# loki.net
KiCad netlist of a schematic drawn in EAGLE
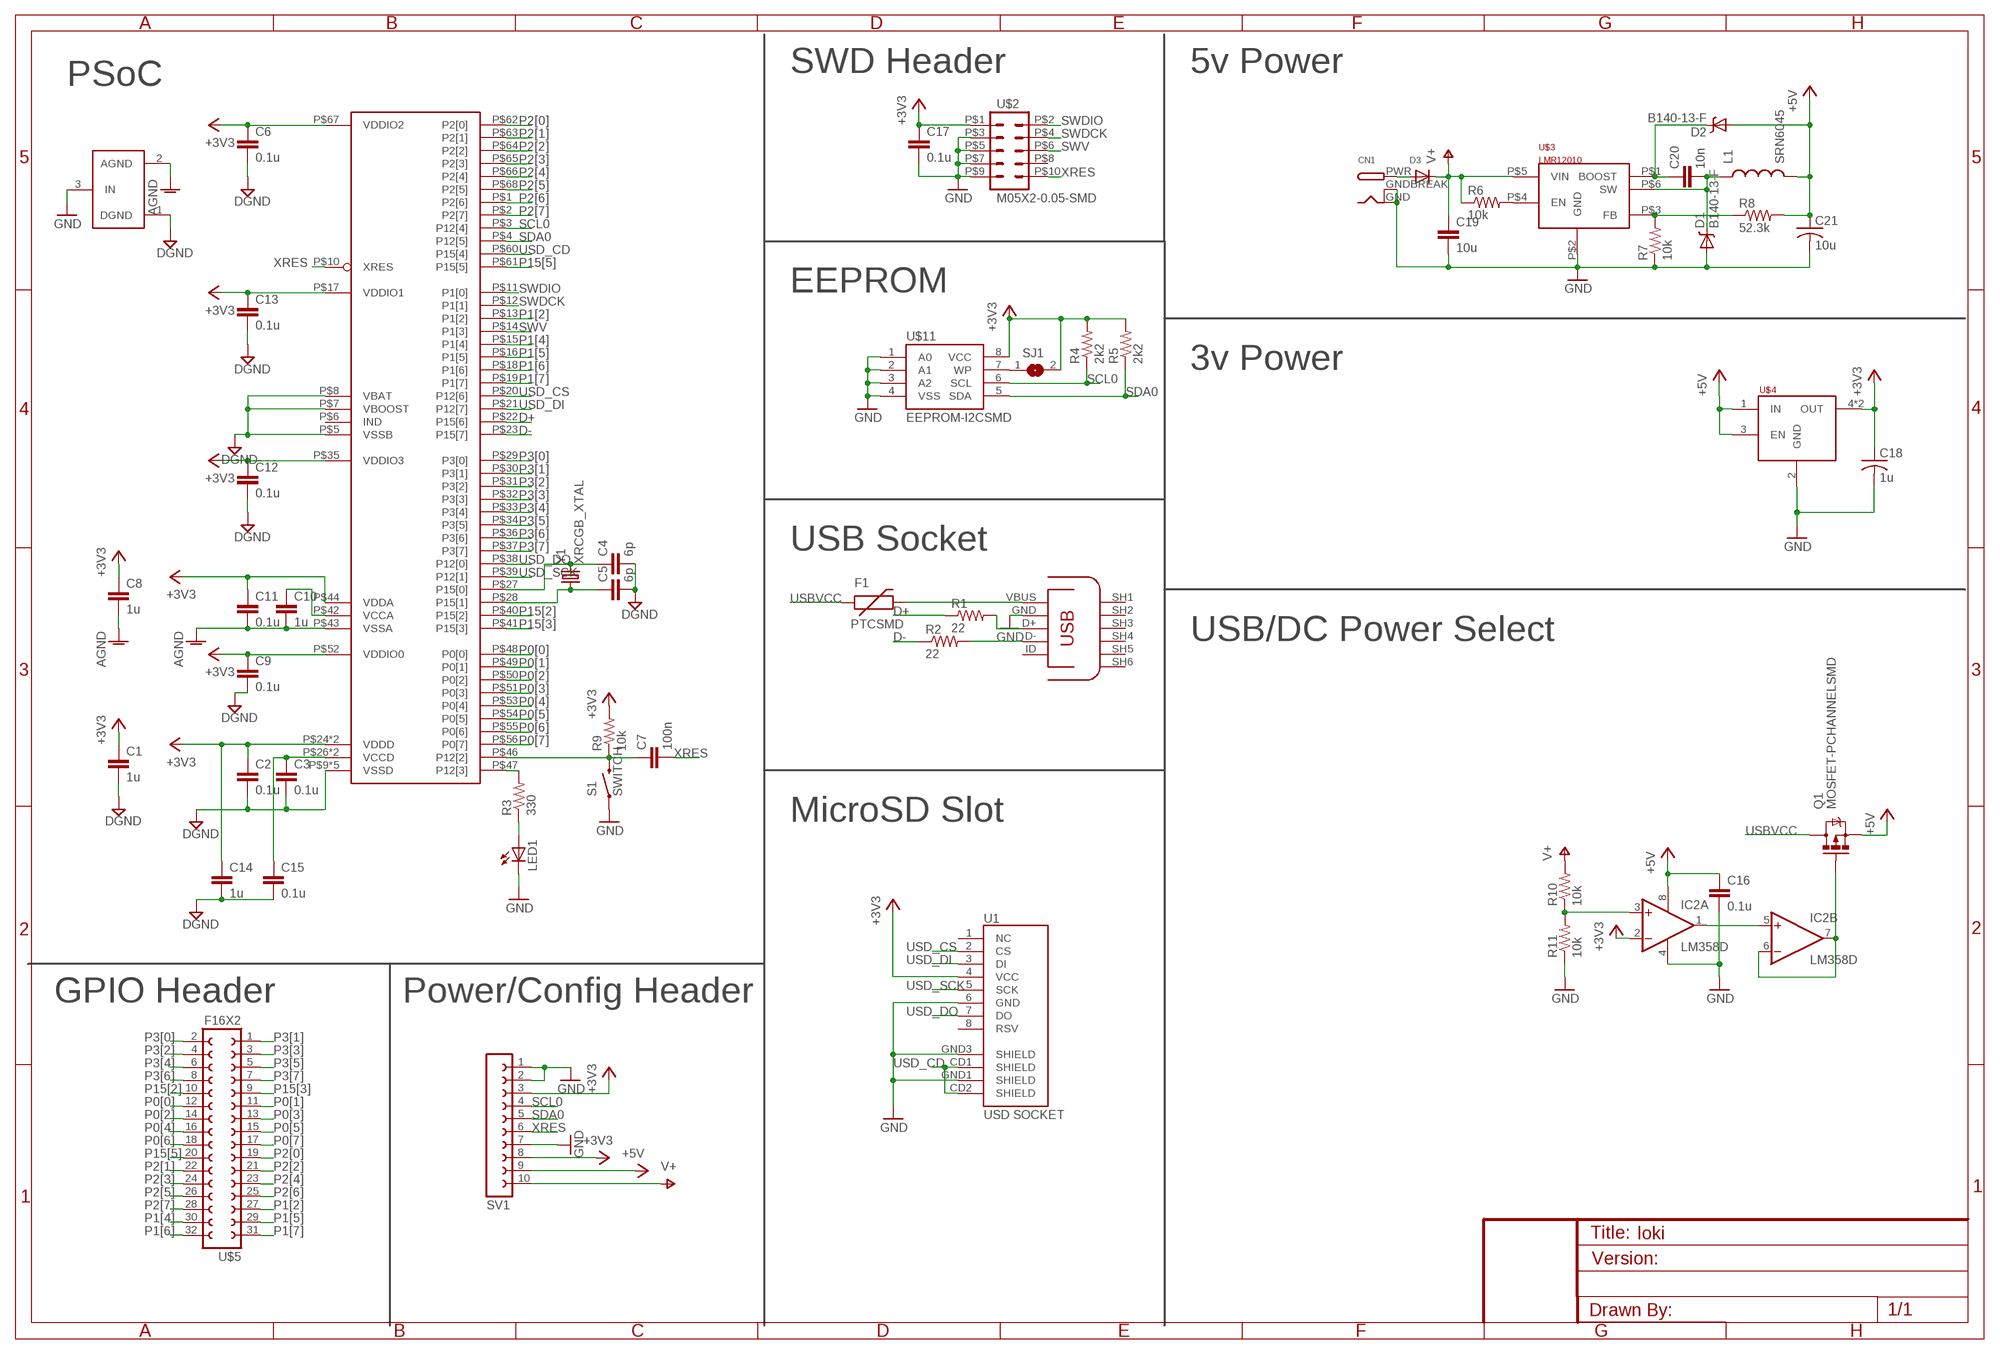
[diagram p0: schematic, sheet 1]

(export (version "E")
  (design (tool "Eeschema 10.0.6"))
  (components
    (comp (ref "C1")
      (value "1u")
      (footprint "eagle-import:C0603K")
      (libsource (lib "eagle-import") (part "C-EUC0603K"))
    )
    (comp (ref "C2")
      (value "0.1u")
      (footprint "eagle-import:C0603K")
      (libsource (lib "eagle-import") (part "C-EUC0603K"))
    )
    (comp (ref "C3")
      (value "0.1u")
      (footprint "eagle-import:C0603K")
      (libsource (lib "eagle-import") (part "C-EUC0603K"))
    )
    (comp (ref "C4")
      (value "6p")
      (footprint "eagle-import:C0603K")
      (libsource (lib "eagle-import") (part "C-EUC0603K"))
    )
    (comp (ref "C5")
      (value "6p")
      (footprint "eagle-import:C0603K")
      (libsource (lib "eagle-import") (part "C-EUC0603K"))
    )
    (comp (ref "C6")
      (value "0.1u")
      (footprint "eagle-import:C0603K")
      (libsource (lib "eagle-import") (part "C-EUC0603K"))
    )
    (comp (ref "C7")
      (value "100n")
      (footprint "eagle-import:C0603K")
      (libsource (lib "eagle-import") (part "C-EUC0603K"))
    )
    (comp (ref "C8")
      (value "1u")
      (footprint "eagle-import:C0603K")
      (libsource (lib "eagle-import") (part "C-EUC0603K"))
    )
    (comp (ref "C9")
      (value "0.1u")
      (footprint "eagle-import:C0603K")
      (libsource (lib "eagle-import") (part "C-EUC0603K"))
    )
    (comp (ref "C10")
      (value "1u")
      (footprint "eagle-import:C0603K")
      (libsource (lib "eagle-import") (part "C-EUC0603K"))
    )
    (comp (ref "C11")
      (value "0.1u")
      (footprint "eagle-import:C0603K")
      (libsource (lib "eagle-import") (part "C-EUC0603K"))
    )
    (comp (ref "C12")
      (value "0.1u")
      (footprint "eagle-import:C0603K")
      (libsource (lib "eagle-import") (part "C-EUC0603K"))
    )
    (comp (ref "C13")
      (value "0.1u")
      (footprint "eagle-import:C0603K")
      (libsource (lib "eagle-import") (part "C-EUC0603K"))
    )
    (comp (ref "C14")
      (value "1u")
      (footprint "eagle-import:C0603K")
      (libsource (lib "eagle-import") (part "C-EUC0603K"))
    )
    (comp (ref "C15")
      (value "0.1u")
      (footprint "eagle-import:C0603K")
      (libsource (lib "eagle-import") (part "C-EUC0603K"))
    )
    (comp (ref "C16")
      (value "0.1u")
      (footprint "eagle-import:0603-CAP")
      (libsource (lib "eagle-import") (part "CAP0603-CAP"))
    )
    (comp (ref "C17")
      (value "0.1u")
      (footprint "eagle-import:C0603K")
      (libsource (lib "eagle-import") (part "C-EUC0603K"))
    )
    (comp (ref "C18")
      (value "1u")
      (footprint "eagle-import:C0603")
      (libsource (lib "eagle-import") (part "C-USC0603"))
    )
    (comp (ref "C19")
      (value "10u")
      (footprint "eagle-import:C1210")
      (libsource (lib "eagle-import") (part "C-EUC1210"))
    )
    (comp (ref "C20")
      (value "10n")
      (footprint "eagle-import:C0805")
      (libsource (lib "eagle-import") (part "C-EUC0805"))
    )
    (comp (ref "C21")
      (value "10u")
      (footprint "eagle-import:C1206")
      (libsource (lib "eagle-import") (part "C-USC1206"))
    )
    (comp (ref "CN1")
      (value "DCBARRELPTH")
      (footprint "eagle-import:DCJACK_2MM_PTH")
      (libsource (lib "eagle-import") (part "DCBARRELPTH"))
    )
    (comp (ref "D1")
      (value "B140-13-F")
      (footprint "eagle-import:SMA-DIODE")
      (libsource (lib "eagle-import") (part "DIODE-SCHOTTKY_"))
    )
    (comp (ref "D2")
      (value "B140-13-F")
      (footprint "eagle-import:SMA-DIODE")
      (libsource (lib "eagle-import") (part "DIODE-SCHOTTKY_"))
    )
    (comp (ref "D3")
      (value "DIODESMA")
      (footprint "eagle-import:SMADIODE")
      (libsource (lib "eagle-import") (part "DIODESMA"))
    )
    (comp (ref "F1")
      (value "PTCSMD")
      (footprint "eagle-import:PTC-1206")
      (libsource (lib "eagle-import") (part "PTCSMD"))
    )
    (comp (ref "IC2")
      (value "LM358D")
      (footprint "eagle-import:SO08")
      (libsource (lib "eagle-import") (part "LM358D"))
    )
    (comp (ref "L1")
      (value "SRN6045")
      (footprint "eagle-import:SRN6045")
      (libsource (lib "eagle-import") (part "SRN6045"))
    )
    (comp (ref "LED1")
      (value "LEDCHIP-LED0805")
      (footprint "eagle-import:CHIP-LED0805")
      (libsource (lib "eagle-import") (part "LEDCHIP-LED0805"))
    )
    (comp (ref "Q1")
      (value "MOSFET-PCHANNELSMD")
      (footprint "eagle-import:SOT23-3")
      (libsource (lib "eagle-import") (part "MOSFET-PCHANNELSMD"))
    )
    (comp (ref "R1")
      (value "22")
      (footprint "eagle-import:0603-RES")
      (libsource (lib "eagle-import") (part "RESISTOR0603-RES"))
    )
    (comp (ref "R2")
      (value "22")
      (footprint "eagle-import:0603-RES")
      (libsource (lib "eagle-import") (part "RESISTOR0603-RES"))
    )
    (comp (ref "R3")
      (value "330")
      (footprint "eagle-import:R0603")
      (libsource (lib "eagle-import") (part "R-US_R0603"))
    )
    (comp (ref "R4")
      (value "2k2")
      (footprint "eagle-import:R0603")
      (libsource (lib "eagle-import") (part "R-US_R0603"))
    )
    (comp (ref "R5")
      (value "2k2")
      (footprint "eagle-import:R0603")
      (libsource (lib "eagle-import") (part "R-US_R0603"))
    )
    (comp (ref "R6")
      (value "10k")
      (footprint "eagle-import:R0603")
      (libsource (lib "eagle-import") (part "R-US_R0603"))
    )
    (comp (ref "R7")
      (value "10k")
      (footprint "eagle-import:R0603")
      (libsource (lib "eagle-import") (part "R-US_R0603"))
    )
    (comp (ref "R8")
      (value "52.3k")
      (footprint "eagle-import:R0603")
      (libsource (lib "eagle-import") (part "R-US_R0603"))
    )
    (comp (ref "R9")
      (value "10k")
      (footprint "eagle-import:R0603")
      (libsource (lib "eagle-import") (part "R-US_R0603"))
    )
    (comp (ref "R10")
      (value "10k")
      (footprint "eagle-import:R0603")
      (libsource (lib "eagle-import") (part "R-US_R0603"))
    )
    (comp (ref "R11")
      (value "10k")
      (footprint "eagle-import:R0603")
      (libsource (lib "eagle-import") (part "R-US_R0603"))
    )
    (comp (ref "S1")
      (value "SWITCH")
      (footprint "eagle-import:TACTILE_SWITCH_SMD")
      (libsource (lib "eagle-import") (part "SWITCH-MOMENTARY-2SMD"))
    )
    (comp (ref "SJ1") (value "SJ") (footprint "eagle-import:SJ") (libsource (lib "eagle-import") (part "SJ")))
    (comp (ref "SV1")
      (value "FE10-1")
      (footprint "eagle-import:FE10")
      (libsource (lib "eagle-import") (part "FE10-1"))
    )
    (comp (ref "U$1")
      (value "CY83XXX-68PIN")
      (footprint "eagle-import:QFN68")
      (libsource (lib "eagle-import") (part "CY83XXX-68PIN"))
    )
    (comp (ref "U$2")
      (value "M05X2-0.05-SMD")
      (footprint "eagle-import:PINHD-2X5-0.05-SMD")
      (libsource (lib "eagle-import") (part "M05X2-0.05-SMD"))
    )
    (comp (ref "U$3")
      (value "LMR12010")
      (footprint "eagle-import:TSOT-6")
      (libsource (lib "eagle-import") (part "LMR12010"))
    )
    (comp (ref "U$4")
      (value "TLV702XX")
      (footprint "eagle-import:SOT23-5")
      (libsource (lib "eagle-import") (part "TLV702XX"))
    )
    (comp (ref "U$5")
      (value "F16X2")
      (footprint "eagle-import:FE16-2")
      (libsource (lib "eagle-import") (part "F16X2"))
    )
    (comp (ref "U$7")
      (value "MICROUSB")
      (footprint "eagle-import:USB-MICROB")
      (libsource (lib "eagle-import") (part "MICROUSB"))
    )
    (comp (ref "U$9")
      (value "GND_CONNECT")
      (footprint "eagle-import:GND_CONNECT")
      (libsource (lib "eagle-import") (part "GND_CONNECT"))
    )
    (comp (ref "U$11")
      (value "EEPROM-I2CSMD")
      (footprint "eagle-import:SO08")
      (libsource (lib "eagle-import") (part "EEPROM-I2CSMD"))
    )
    (comp (ref "U1")
      (value "USD SOCKET")
      (footprint "eagle-import:MICRO-SD-SOCKET-PP")
      (libsource (lib "eagle-import") (part "USD-SOCKETNEW"))
    )
    (comp (ref "Y1")
      (value "XRCGB_XTAL")
      (footprint "eagle-import:XRCGB-XTAL")
      (libsource (lib "eagle-import") (part "XRCGB_XTAL"))
    )
  )
  (nets
    (net (code "1") (name "+3V3") (class "Default")
      (node (ref "C1") (pin "1") (pinfunction "1_1") (pintype "passive"))
      (node (ref "C11") (pin "1") (pinfunction "1_1") (pintype "passive"))
      (node (ref "C12") (pin "1") (pinfunction "1_1") (pintype "passive"))
      (node (ref "C13") (pin "1") (pinfunction "1_1") (pintype "passive"))
      (node (ref "C14") (pin "1") (pinfunction "1_1") (pintype "passive"))
      (node (ref "C17") (pin "1") (pinfunction "1_1") (pintype "passive"))
      (node (ref "C18") (pin "1") (pinfunction "1_1") (pintype "passive"))
      (node (ref "C2") (pin "1") (pinfunction "1_1") (pintype "passive"))
      (node (ref "C6") (pin "1") (pinfunction "1_1") (pintype "passive"))
      (node (ref "C8") (pin "1") (pinfunction "1_1") (pintype "passive"))
      (node (ref "C9") (pin "1") (pinfunction "1_1") (pintype "passive"))
      (node (ref "IC2") (pin "2") (pinfunction "-IN_2") (pintype "input"))
      (node (ref "R4") (pin "2") (pinfunction "2_2") (pintype "passive"))
      (node (ref "R5") (pin "2") (pinfunction "2_2") (pintype "passive"))
      (node (ref "R9") (pin "2") (pinfunction "2_2") (pintype "passive"))
      (node (ref "SJ1") (pin "2") (pinfunction "2_2") (pintype "passive"))
      (node (ref "SV1") (pin "3") (pinfunction "3_3") (pintype "passive"))
      (node (ref "SV1") (pin "8") (pinfunction "8_8") (pintype "passive"))
      (node (ref "U$1") (pin "P$17") (pinfunction "VDDIO1_P$17") (pintype "power_in"))
      (node (ref "U$1") (pin "P$24") (pinfunction "VDDD_P$24") (pintype "power_in"))
      (node (ref "U$1") (pin "P$35") (pinfunction "VDDIO3_P$35") (pintype "power_in"))
      (node (ref "U$1") (pin "P$44") (pinfunction "VDDA_P$44") (pintype "power_in"))
      (node (ref "U$1") (pin "P$52") (pinfunction "VDDIO0_P$52") (pintype "power_in"))
      (node (ref "U$1") (pin "P$59") (pinfunction "VDDD_P$59") (pintype "power_in"))
      (node (ref "U$1") (pin "P$67") (pinfunction "VDDIO2_P$67") (pintype "power_in"))
      (node (ref "U$11") (pin "8") (pinfunction "VCC_8") (pintype "power_in"))
      (node (ref "U$2") (pin "P$1") (pinfunction "1_P$1") (pintype "passive"))
      (node (ref "U$4") (pin "4") (pinfunction "OUT_4") (pintype "power_in"))
      (node (ref "U$4") (pin "5") (pinfunction "OUT_5") (pintype "power_in"))
      (node (ref "U1") (pin "4") (pinfunction "VCC_4") (pintype "bidirectional"))
    )
    (net (code "2") (name "+5V") (class "Default")
      (node (ref "C16") (pin "1") (pinfunction "1_1") (pintype "passive"))
      (node (ref "C21") (pin "1") (pinfunction "1_1") (pintype "passive"))
      (node (ref "D2") (pin "A") (pinfunction "A_A") (pintype "passive"))
      (node (ref "IC2") (pin "8") (pinfunction "V+_8") (pintype "power_in"))
      (node (ref "L1") (pin "P$2") (pinfunction "2_P$2") (pintype "passive"))
      (node (ref "Q1") (pin "2") (pinfunction "S_2") (pintype "passive"))
      (node (ref "R8") (pin "2") (pinfunction "2_2") (pintype "passive"))
      (node (ref "SV1") (pin "9") (pinfunction "9_9") (pintype "passive"))
      (node (ref "U$4") (pin "1") (pinfunction "IN_1") (pintype "power_in"))
      (node (ref "U$4") (pin "3") (pinfunction "EN_3") (pintype "input"))
    )
    (net (code "3") (name "/D+") (class "Default")
      (node (ref "R1") (pin "1") (pinfunction "1_1") (pintype "passive"))
      (node (ref "U$1") (pin "P$22") (pinfunction "P15[6]_P$22") (pintype "bidirectional"))
    )
    (net (code "4") (name "/D-") (class "Default")
      (node (ref "R2") (pin "1") (pinfunction "1_1") (pintype "passive"))
      (node (ref "U$1") (pin "P$23") (pinfunction "P15[7]_P$23") (pintype "bidirectional"))
    )
    (net (code "5") (name "/IND") (class "Default")
      (node (ref "U$1") (pin "P$6") (pinfunction "IND_P$6") (pintype "power_in"))
    )
    (net (code "6") (name "/P0[0]") (class "Default")
      (node (ref "U$1") (pin "P$48") (pinfunction "P0[0]_P$48") (pintype "bidirectional"))
      (node (ref "U$5") (pin "12") (pinfunction "12_12") (pintype "passive"))
    )
    (net (code "7") (name "/P0[1]") (class "Default")
      (node (ref "U$1") (pin "P$49") (pinfunction "P0[1]_P$49") (pintype "bidirectional"))
      (node (ref "U$5") (pin "11") (pinfunction "11_11") (pintype "passive"))
    )
    (net (code "8") (name "/P0[2]") (class "Default")
      (node (ref "U$1") (pin "P$50") (pinfunction "P0[2]_P$50") (pintype "bidirectional"))
      (node (ref "U$5") (pin "14") (pinfunction "14_14") (pintype "passive"))
    )
    (net (code "9") (name "/P0[3]") (class "Default")
      (node (ref "U$1") (pin "P$51") (pinfunction "P0[3]_P$51") (pintype "bidirectional"))
      (node (ref "U$5") (pin "13") (pinfunction "13_13") (pintype "passive"))
    )
    (net (code "10") (name "/P0[4]") (class "Default")
      (node (ref "U$1") (pin "P$53") (pinfunction "P0[4]_P$53") (pintype "bidirectional"))
      (node (ref "U$5") (pin "16") (pinfunction "16_16") (pintype "passive"))
    )
    (net (code "11") (name "/P0[5]") (class "Default")
      (node (ref "U$1") (pin "P$54") (pinfunction "P0[5]_P$54") (pintype "bidirectional"))
      (node (ref "U$5") (pin "15") (pinfunction "15_15") (pintype "passive"))
    )
    (net (code "12") (name "/P0[6]") (class "Default")
      (node (ref "U$1") (pin "P$55") (pinfunction "P0[6]_P$55") (pintype "bidirectional"))
      (node (ref "U$5") (pin "18") (pinfunction "18_18") (pintype "passive"))
    )
    (net (code "13") (name "/P0[7]") (class "Default")
      (node (ref "U$1") (pin "P$56") (pinfunction "P0[7]_P$56") (pintype "bidirectional"))
      (node (ref "U$5") (pin "17") (pinfunction "17_17") (pintype "passive"))
    )
    (net (code "14") (name "/P1[2]") (class "Default")
      (node (ref "U$1") (pin "P$13") (pinfunction "P1[2]_P$13") (pintype "bidirectional"))
      (node (ref "U$5") (pin "27") (pinfunction "27_27") (pintype "passive"))
    )
    (net (code "15") (name "/P1[4]") (class "Default")
      (node (ref "U$1") (pin "P$15") (pinfunction "P1[4]_P$15") (pintype "bidirectional"))
      (node (ref "U$5") (pin "30") (pinfunction "30_30") (pintype "passive"))
    )
    (net (code "16") (name "/P1[5]") (class "Default")
      (node (ref "U$1") (pin "P$16") (pinfunction "P1[5]_P$16") (pintype "bidirectional"))
      (node (ref "U$5") (pin "29") (pinfunction "29_29") (pintype "passive"))
    )
    (net (code "17") (name "/P1[6]") (class "Default")
      (node (ref "U$1") (pin "P$18") (pinfunction "P1[6]_P$18") (pintype "bidirectional"))
      (node (ref "U$5") (pin "32") (pinfunction "32_32") (pintype "passive"))
    )
    (net (code "18") (name "/P1[7]") (class "Default")
      (node (ref "U$1") (pin "P$19") (pinfunction "P1[7]_P$19") (pintype "bidirectional"))
      (node (ref "U$5") (pin "31") (pinfunction "31_31") (pintype "passive"))
    )
    (net (code "19") (name "/P2[0]") (class "Default")
      (node (ref "U$1") (pin "P$62") (pinfunction "P2[0]_P$62") (pintype "bidirectional"))
      (node (ref "U$5") (pin "19") (pinfunction "19_19") (pintype "passive"))
    )
    (net (code "20") (name "/P2[1]") (class "Default")
      (node (ref "U$1") (pin "P$63") (pinfunction "P2[1]_P$63") (pintype "bidirectional"))
      (node (ref "U$5") (pin "22") (pinfunction "22_22") (pintype "passive"))
    )
    (net (code "21") (name "/P2[2]") (class "Default")
      (node (ref "U$1") (pin "P$64") (pinfunction "P2[2]_P$64") (pintype "bidirectional"))
      (node (ref "U$5") (pin "21") (pinfunction "21_21") (pintype "passive"))
    )
    (net (code "22") (name "/P2[3]") (class "Default")
      (node (ref "U$1") (pin "P$65") (pinfunction "P2[3]_P$65") (pintype "bidirectional"))
      (node (ref "U$5") (pin "24") (pinfunction "24_24") (pintype "passive"))
    )
    (net (code "23") (name "/P2[4]") (class "Default")
      (node (ref "U$1") (pin "P$66") (pinfunction "P2[4]_P$66") (pintype "bidirectional"))
      (node (ref "U$5") (pin "23") (pinfunction "23_23") (pintype "passive"))
    )
    (net (code "24") (name "/P2[5]") (class "Default")
      (node (ref "U$1") (pin "P$68") (pinfunction "P2[5]_P$68") (pintype "bidirectional"))
      (node (ref "U$5") (pin "26") (pinfunction "26_26") (pintype "passive"))
    )
    (net (code "25") (name "/P2[6]") (class "Default")
      (node (ref "U$1") (pin "P$1") (pinfunction "P2[6]_P$1") (pintype "bidirectional"))
      (node (ref "U$5") (pin "25") (pinfunction "25_25") (pintype "passive"))
    )
    (net (code "26") (name "/P2[7]") (class "Default")
      (node (ref "U$1") (pin "P$2") (pinfunction "P2[7]_P$2") (pintype "bidirectional"))
      (node (ref "U$5") (pin "28") (pinfunction "28_28") (pintype "passive"))
    )
    (net (code "27") (name "/P3[0]") (class "Default")
      (node (ref "U$1") (pin "P$29") (pinfunction "P3[0]_P$29") (pintype "bidirectional"))
      (node (ref "U$5") (pin "2") (pinfunction "2_2") (pintype "passive"))
    )
    (net (code "28") (name "/P3[1]") (class "Default")
      (node (ref "U$1") (pin "P$30") (pinfunction "P3[1]_P$30") (pintype "bidirectional"))
      (node (ref "U$5") (pin "1") (pinfunction "1_1") (pintype "passive"))
    )
    (net (code "29") (name "/P3[2]") (class "Default")
      (node (ref "U$1") (pin "P$31") (pinfunction "P3[2]_P$31") (pintype "bidirectional"))
      (node (ref "U$5") (pin "4") (pinfunction "4_4") (pintype "passive"))
    )
    (net (code "30") (name "/P3[3]") (class "Default")
      (node (ref "U$1") (pin "P$32") (pinfunction "P3[3]_P$32") (pintype "bidirectional"))
      (node (ref "U$5") (pin "3") (pinfunction "3_3") (pintype "passive"))
    )
    (net (code "31") (name "/P3[4]") (class "Default")
      (node (ref "U$1") (pin "P$33") (pinfunction "P3[4]_P$33") (pintype "bidirectional"))
      (node (ref "U$5") (pin "6") (pinfunction "6_6") (pintype "passive"))
    )
    (net (code "32") (name "/P3[5]") (class "Default")
      (node (ref "U$1") (pin "P$34") (pinfunction "P3[5]_P$34") (pintype "bidirectional"))
      (node (ref "U$5") (pin "5") (pinfunction "5_5") (pintype "passive"))
    )
    (net (code "33") (name "/P3[6]") (class "Default")
      (node (ref "U$1") (pin "P$36") (pinfunction "P3[6]_P$36") (pintype "bidirectional"))
      (node (ref "U$5") (pin "8") (pinfunction "8_8") (pintype "passive"))
    )
    (net (code "34") (name "/P3[7]") (class "Default")
      (node (ref "U$1") (pin "P$37") (pinfunction "P3[7]_P$37") (pintype "bidirectional"))
      (node (ref "U$5") (pin "7") (pinfunction "7_7") (pintype "passive"))
    )
    (net (code "35") (name "/P15[2]") (class "Default")
      (node (ref "U$1") (pin "P$40") (pinfunction "P15[2]_P$40") (pintype "bidirectional"))
      (node (ref "U$5") (pin "10") (pinfunction "10_10") (pintype "passive"))
    )
    (net (code "36") (name "/P15[3]") (class "Default")
      (node (ref "U$1") (pin "P$41") (pinfunction "P15[3]_P$41") (pintype "bidirectional"))
      (node (ref "U$5") (pin "9") (pinfunction "9_9") (pintype "passive"))
    )
    (net (code "37") (name "/P15[5]") (class "Default")
      (node (ref "U$1") (pin "P$61") (pinfunction "P15[5]_P$61") (pintype "bidirectional"))
      (node (ref "U$5") (pin "20") (pinfunction "20_20") (pintype "passive"))
    )
    (net (code "38") (name "/SCL0") (class "Default")
      (node (ref "R4") (pin "1") (pinfunction "1_1") (pintype "passive"))
      (node (ref "SV1") (pin "4") (pinfunction "4_4") (pintype "passive"))
      (node (ref "U$1") (pin "P$3") (pinfunction "P12[4]_P$3") (pintype "bidirectional"))
      (node (ref "U$11") (pin "6") (pinfunction "SCL_6") (pintype "bidirectional"))
    )
    (net (code "39") (name "/SDA0") (class "Default")
      (node (ref "R5") (pin "1") (pinfunction "1_1") (pintype "passive"))
      (node (ref "SV1") (pin "5") (pinfunction "5_5") (pintype "passive"))
      (node (ref "U$1") (pin "P$4") (pinfunction "P12[5]_P$4") (pintype "bidirectional"))
      (node (ref "U$11") (pin "5") (pinfunction "SDA_5") (pintype "bidirectional"))
    )
    (net (code "40") (name "/SWDCK") (class "Default")
      (node (ref "U$1") (pin "P$12") (pinfunction "P1[1]_P$12") (pintype "bidirectional"))
      (node (ref "U$2") (pin "P$4") (pinfunction "4_P$4") (pintype "passive"))
    )
    (net (code "41") (name "/SWDIO") (class "Default")
      (node (ref "U$1") (pin "P$11") (pinfunction "P1[0]_P$11") (pintype "bidirectional"))
      (node (ref "U$2") (pin "P$2") (pinfunction "2_P$2") (pintype "passive"))
    )
    (net (code "42") (name "/SWV") (class "Default")
      (node (ref "U$1") (pin "P$14") (pinfunction "P1[3]_P$14") (pintype "bidirectional"))
      (node (ref "U$2") (pin "P$6") (pinfunction "6_P$6") (pintype "passive"))
    )
    (net (code "43") (name "/USBVCC") (class "Default")
      (node (ref "F1") (pin "1") (pinfunction "1_1") (pintype "bidirectional"))
      (node (ref "Q1") (pin "3") (pinfunction "D_3") (pintype "passive"))
    )
    (net (code "44") (name "/USD_CD") (class "Default")
      (node (ref "U$1") (pin "P$60") (pinfunction "P15[4]_P$60") (pintype "bidirectional"))
      (node (ref "U1") (pin "CD1") (pinfunction "SHIELD_CD1") (pintype "bidirectional"))
      (node (ref "U1") (pin "CD2") (pinfunction "SHIELD_CD2") (pintype "bidirectional"))
    )
    (net (code "45") (name "/USD_CS") (class "Default")
      (node (ref "U$1") (pin "P$20") (pinfunction "P12[6]_P$20") (pintype "bidirectional"))
      (node (ref "U1") (pin "2") (pinfunction "CS_2") (pintype "bidirectional"))
    )
    (net (code "46") (name "/USD_DI") (class "Default")
      (node (ref "U$1") (pin "P$21") (pinfunction "P12[7]_P$21") (pintype "bidirectional"))
      (node (ref "U1") (pin "3") (pinfunction "DI_3") (pintype "bidirectional"))
    )
    (net (code "47") (name "/USD_DO") (class "Default")
      (node (ref "U$1") (pin "P$38") (pinfunction "P12[0]_P$38") (pintype "bidirectional"))
      (node (ref "U1") (pin "7") (pinfunction "DO_7") (pintype "bidirectional"))
    )
    (net (code "48") (name "/USD_SCK") (class "Default")
      (node (ref "U$1") (pin "P$39") (pinfunction "P12[1]_P$39") (pintype "bidirectional"))
      (node (ref "U1") (pin "5") (pinfunction "SCK_5") (pintype "bidirectional"))
    )
    (net (code "49") (name "/XRES") (class "Default")
      (node (ref "C7") (pin "2") (pinfunction "2_2") (pintype "passive"))
      (node (ref "SV1") (pin "6") (pinfunction "6_6") (pintype "passive"))
      (node (ref "U$1") (pin "P$10") (pinfunction "XRES_P$10") (pintype "input"))
      (node (ref "U$2") (pin "P$10") (pinfunction "10_P$10") (pintype "passive"))
    )
    (net (code "50") (name "AGND") (class "Default")
      (node (ref "C10") (pin "2") (pinfunction "2_2") (pintype "passive"))
      (node (ref "C11") (pin "2") (pinfunction "2_2") (pintype "passive"))
      (node (ref "C8") (pin "2") (pinfunction "2_2") (pintype "passive"))
      (node (ref "U$1") (pin "P$43") (pinfunction "VSSA_P$43") (pintype "power_in"))
      (node (ref "U$9") (pin "2") (pinfunction "AGND_2") (pintype "bidirectional"))
    )
    (net (code "51") (name "DGND") (class "Default")
      (node (ref "C1") (pin "2") (pinfunction "2_2") (pintype "passive"))
      (node (ref "C12") (pin "2") (pinfunction "2_2") (pintype "passive"))
      (node (ref "C13") (pin "2") (pinfunction "2_2") (pintype "passive"))
      (node (ref "C14") (pin "2") (pinfunction "2_2") (pintype "passive"))
      (node (ref "C15") (pin "2") (pinfunction "2_2") (pintype "passive"))
      (node (ref "C2") (pin "2") (pinfunction "2_2") (pintype "passive"))
      (node (ref "C3") (pin "2") (pinfunction "2_2") (pintype "passive"))
      (node (ref "C4") (pin "2") (pinfunction "2_2") (pintype "passive"))
      (node (ref "C5") (pin "2") (pinfunction "2_2") (pintype "passive"))
      (node (ref "C6") (pin "2") (pinfunction "2_2") (pintype "passive"))
      (node (ref "C9") (pin "2") (pinfunction "2_2") (pintype "passive"))
      (node (ref "U$1") (pin "P$25") (pinfunction "VSSD_P$25") (pintype "power_in"))
      (node (ref "U$1") (pin "P$45") (pinfunction "VSSD_P$45") (pintype "power_in"))
      (node (ref "U$1") (pin "P$5") (pinfunction "VSSB_P$5") (pintype "power_in"))
      (node (ref "U$1") (pin "P$58") (pinfunction "VSSD_P$58") (pintype "power_in"))
      (node (ref "U$1") (pin "P$7") (pinfunction "VBOOST_P$7") (pintype "power_in"))
      (node (ref "U$1") (pin "P$8") (pinfunction "VBAT_P$8") (pintype "power_in"))
      (node (ref "U$1") (pin "P$9") (pinfunction "VSSD_P$9") (pintype "power_in"))
      (node (ref "U$1") (pin "P$CENTER") (pinfunction "VSSD_P$CENTER") (pintype "power_in"))
      (node (ref "U$9") (pin "1") (pinfunction "DGND_1") (pintype "bidirectional"))
    )
    (net (code "52") (name "GND") (class "Default")
      (node (ref "C16") (pin "2") (pinfunction "2_2") (pintype "passive"))
      (node (ref "C17") (pin "2") (pinfunction "2_2") (pintype "passive"))
      (node (ref "C18") (pin "2") (pinfunction "2_2") (pintype "passive"))
      (node (ref "C19") (pin "2") (pinfunction "2_2") (pintype "passive"))
      (node (ref "C21") (pin "2") (pinfunction "2_2") (pintype "passive"))
      (node (ref "CN1") (pin "GND") (pinfunction "GND_GND") (pintype "power_in"))
      (node (ref "CN1") (pin "GNDBREAK") (pinfunction "GNDBREAK_GNDBREAK") (pintype "power_in"))
      (node (ref "D1") (pin "A") (pinfunction "A_A") (pintype "passive"))
      (node (ref "IC2") (pin "4") (pinfunction "V-_4") (pintype "power_in"))
      (node (ref "LED1") (pin "C") (pinfunction "C_C") (pintype "passive"))
      (node (ref "R11") (pin "1") (pinfunction "1_1") (pintype "passive"))
      (node (ref "R7") (pin "1") (pinfunction "1_1") (pintype "passive"))
      (node (ref "S1") (pin "1") (pinfunction "1_1") (pintype "passive"))
      (node (ref "SV1") (pin "1") (pinfunction "1_1") (pintype "passive"))
      (node (ref "SV1") (pin "2") (pinfunction "2_2") (pintype "passive"))
      (node (ref "SV1") (pin "7") (pinfunction "7_7") (pintype "passive"))
      (node (ref "U$11") (pin "1") (pinfunction "A0_1") (pintype "bidirectional"))
      (node (ref "U$11") (pin "2") (pinfunction "A1_2") (pintype "bidirectional"))
      (node (ref "U$11") (pin "3") (pinfunction "A2_3") (pintype "bidirectional"))
      (node (ref "U$11") (pin "4") (pinfunction "VSS_4") (pintype "power_in"))
      (node (ref "U$2") (pin "P$3") (pinfunction "3_P$3") (pintype "passive"))
      (node (ref "U$2") (pin "P$5") (pinfunction "5_P$5") (pintype "passive"))
      (node (ref "U$2") (pin "P$7") (pinfunction "7_P$7") (pintype "passive"))
      (node (ref "U$2") (pin "P$9") (pinfunction "9_P$9") (pintype "passive"))
      (node (ref "U$3") (pin "P$2") (pinfunction "GND_P$2") (pintype "power_in"))
      (node (ref "U$4") (pin "2") (pinfunction "GND_2") (pintype "power_in"))
      (node (ref "U$7") (pin "GND") (pinfunction "GND_GND") (pintype "bidirectional"))
      (node (ref "U$9") (pin "3") (pinfunction "IN_3") (pintype "bidirectional"))
      (node (ref "U1") (pin "6") (pinfunction "GND_6") (pintype "bidirectional"))
      (node (ref "U1") (pin "GND1") (pinfunction "SHIELD_GND1") (pintype "bidirectional"))
      (node (ref "U1") (pin "GND3") (pinfunction "SHIELD_GND3") (pintype "bidirectional"))
    )
    (net (code "53") (name "Net-(C15-Pad1)") (class "Default")
      (node (ref "C15") (pin "1") (pinfunction "1_1") (pintype "passive"))
      (node (ref "C3") (pin "1") (pinfunction "1_1") (pintype "passive"))
      (node (ref "U$1") (pin "P$26") (pinfunction "VCCD_P$26") (pintype "power_in"))
      (node (ref "U$1") (pin "P$57") (pinfunction "VCCD_P$57") (pintype "power_in"))
    )
    (net (code "54") (name "Net-(CN1-PadPWR)") (class "Default")
      (node (ref "CN1") (pin "PWR") (pinfunction "PWR_PWR") (pintype "power_in"))
      (node (ref "D3") (pin "A") (pinfunction "A_A") (pintype "passive"))
    )
    (net (code "55") (name "Net-(IC2A-+IN)") (class "Default")
      (node (ref "IC2") (pin "3") (pinfunction "+IN_3") (pintype "input"))
      (node (ref "R10") (pin "1") (pinfunction "1_1") (pintype "passive"))
      (node (ref "R11") (pin "2") (pinfunction "2_2") (pintype "passive"))
    )
    (net (code "56") (name "Net-(IC2A-OUT)") (class "Default")
      (node (ref "IC2") (pin "1") (pinfunction "OUT_1") (pintype "output"))
      (node (ref "IC2") (pin "5") (pinfunction "+IN_5") (pintype "input"))
    )
    (net (code "57") (name "Net-(IC2B--IN)") (class "Default")
      (node (ref "IC2") (pin "6") (pinfunction "-IN_6") (pintype "input"))
      (node (ref "IC2") (pin "7") (pinfunction "OUT_7") (pintype "output"))
      (node (ref "Q1") (pin "1") (pinfunction "G_1") (pintype "passive"))
    )
    (net (code "58") (name "Net-(L1-1)") (class "Default")
      (node (ref "C20") (pin "2") (pinfunction "2_2") (pintype "passive"))
      (node (ref "D1") (pin "C") (pinfunction "C_C") (pintype "passive"))
      (node (ref "L1") (pin "P$1") (pinfunction "1_P$1") (pintype "passive"))
      (node (ref "U$3") (pin "P$6") (pinfunction "SW_P$6") (pintype "power_in"))
    )
    (net (code "59") (name "Net-(LED1-PadA)") (class "Default")
      (node (ref "LED1") (pin "A") (pinfunction "A_A") (pintype "passive"))
      (node (ref "R3") (pin "1") (pinfunction "1_1") (pintype "passive"))
    )
    (net (code "60") (name "Net-(R1-Pad2)") (class "Default")
      (node (ref "R1") (pin "2") (pinfunction "2_2") (pintype "passive"))
      (node (ref "U$7") (pin "D+") (pinfunction "D+_D+") (pintype "bidirectional"))
    )
    (net (code "61") (name "Net-(R2-Pad2)") (class "Default")
      (node (ref "R2") (pin "2") (pinfunction "2_2") (pintype "passive"))
      (node (ref "U$7") (pin "D-") (pinfunction "D-_D-") (pintype "bidirectional"))
    )
    (net (code "62") (name "Net-(S1-2)") (class "Default")
      (node (ref "C7") (pin "1") (pinfunction "1_1") (pintype "passive"))
      (node (ref "R9") (pin "1") (pinfunction "1_1") (pintype "passive"))
      (node (ref "S1") (pin "3") (pinfunction "2_3") (pintype "passive"))
      (node (ref "U$1") (pin "P$46") (pinfunction "P12[2]_P$46") (pintype "bidirectional"))
    )
    (net (code "63") (name "Net-(U$1-P12[3])") (class "Default")
      (node (ref "R3") (pin "2") (pinfunction "2_2") (pintype "passive"))
      (node (ref "U$1") (pin "P$47") (pinfunction "P12[3]_P$47") (pintype "bidirectional"))
    )
    (net (code "64") (name "Net-(U$1-P15[0])") (class "Default")
      (node (ref "C4") (pin "1") (pinfunction "1_1") (pintype "passive"))
      (node (ref "U$1") (pin "P$27") (pinfunction "P15[0]_P$27") (pintype "bidirectional"))
      (node (ref "Y1") (pin "2") (pinfunction "2_2") (pintype "passive"))
    )
    (net (code "65") (name "Net-(U$1-P15[1])") (class "Default")
      (node (ref "C5") (pin "1") (pinfunction "1_1") (pintype "passive"))
      (node (ref "U$1") (pin "P$28") (pinfunction "P15[1]_P$28") (pintype "bidirectional"))
      (node (ref "Y1") (pin "1") (pinfunction "1_1") (pintype "passive"))
    )
    (net (code "66") (name "Net-(U$1-VCCA)") (class "Default")
      (node (ref "C10") (pin "1") (pinfunction "1_1") (pintype "passive"))
      (node (ref "U$1") (pin "P$42") (pinfunction "VCCA_P$42") (pintype "power_in"))
    )
    (net (code "67") (name "Net-(U$3-BOOST)") (class "Default")
      (node (ref "C20") (pin "1") (pinfunction "1_1") (pintype "passive"))
      (node (ref "D2") (pin "C") (pinfunction "C_C") (pintype "passive"))
      (node (ref "U$3") (pin "P$1") (pinfunction "BOOST_P$1") (pintype "input"))
    )
    (net (code "68") (name "Net-(U$3-EN)") (class "Default")
      (node (ref "R6") (pin "2") (pinfunction "2_2") (pintype "passive"))
      (node (ref "U$3") (pin "P$4") (pinfunction "EN_P$4") (pintype "input"))
    )
    (net (code "69") (name "Net-(U$3-FB)") (class "Default")
      (node (ref "R7") (pin "2") (pinfunction "2_2") (pintype "passive"))
      (node (ref "R8") (pin "1") (pinfunction "1_1") (pintype "passive"))
      (node (ref "U$3") (pin "P$3") (pinfunction "FB_P$3") (pintype "input"))
    )
    (net (code "70") (name "Net-(U$7-VCC)") (class "Default")
      (node (ref "F1") (pin "2") (pinfunction "2_2") (pintype "bidirectional"))
      (node (ref "U$7") (pin "VBUS") (pinfunction "VCC_VBUS") (pintype "bidirectional"))
    )
    (net (code "71") (name "Net-(U$11-WP)") (class "Default")
      (node (ref "SJ1") (pin "1") (pinfunction "1_1") (pintype "passive"))
      (node (ref "U$11") (pin "7") (pinfunction "WP_7") (pintype "bidirectional"))
    )
    (net (code "72") (name "V+") (class "Default")
      (node (ref "C19") (pin "1") (pinfunction "1_1") (pintype "passive"))
      (node (ref "D3") (pin "C") (pinfunction "C_C") (pintype "passive"))
      (node (ref "R10") (pin "2") (pinfunction "2_2") (pintype "passive"))
      (node (ref "R6") (pin "1") (pinfunction "1_1") (pintype "passive"))
      (node (ref "SV1") (pin "10") (pinfunction "10_10") (pintype "passive"))
      (node (ref "U$3") (pin "P$5") (pinfunction "VIN_P$5") (pintype "power_in"))
    )
    (net (code "73") (name "unconnected-(U$2-8-PadP$8)") (class "Default")
      (node (ref "U$2") (pin "P$8") (pinfunction "8_P$8") (pintype "passive"))
    )
    (net (code "74") (name "unconnected-(U$7-PadID)") (class "Default")
      (node (ref "U$7") (pin "ID") (pinfunction "ID_ID") (pintype "bidirectional"))
    )
    (net (code "75") (name "unconnected-(U$7-SH-PadSH1)") (class "Default")
      (node (ref "U$7") (pin "SH1") (pinfunction "SH_SH1") (pintype "bidirectional"))
    )
    (net (code "76") (name "unconnected-(U$7-SH-PadSH2)") (class "Default")
      (node (ref "U$7") (pin "SH2") (pinfunction "SH_SH2") (pintype "bidirectional"))
    )
    (net (code "77") (name "unconnected-(U$7-SH-PadSH3)") (class "Default")
      (node (ref "U$7") (pin "SH3") (pinfunction "SH_SH3") (pintype "bidirectional"))
    )
    (net (code "78") (name "unconnected-(U$7-SH-PadSH4)") (class "Default")
      (node (ref "U$7") (pin "SH4") (pinfunction "SH_SH4") (pintype "bidirectional"))
    )
    (net (code "79") (name "unconnected-(U$7-SH-PadSH5)") (class "Default")
      (node (ref "U$7") (pin "SH5") (pinfunction "SH_SH5") (pintype "bidirectional"))
    )
    (net (code "80") (name "unconnected-(U$7-SH-PadSH6)") (class "Default")
      (node (ref "U$7") (pin "SH6") (pinfunction "SH_SH6") (pintype "bidirectional"))
    )
    (net (code "81") (name "unconnected-(U1-NC-Pad1)") (class "Default")
      (node (ref "U1") (pin "1") (pinfunction "NC_1") (pintype "bidirectional"))
    )
    (net (code "82") (name "unconnected-(U1-RSV-Pad8)") (class "Default")
      (node (ref "U1") (pin "8") (pinfunction "RSV_8") (pintype "bidirectional"))
    )
  )
)
